# master.net
KiCad netlist of a schematic drawn in EAGLE
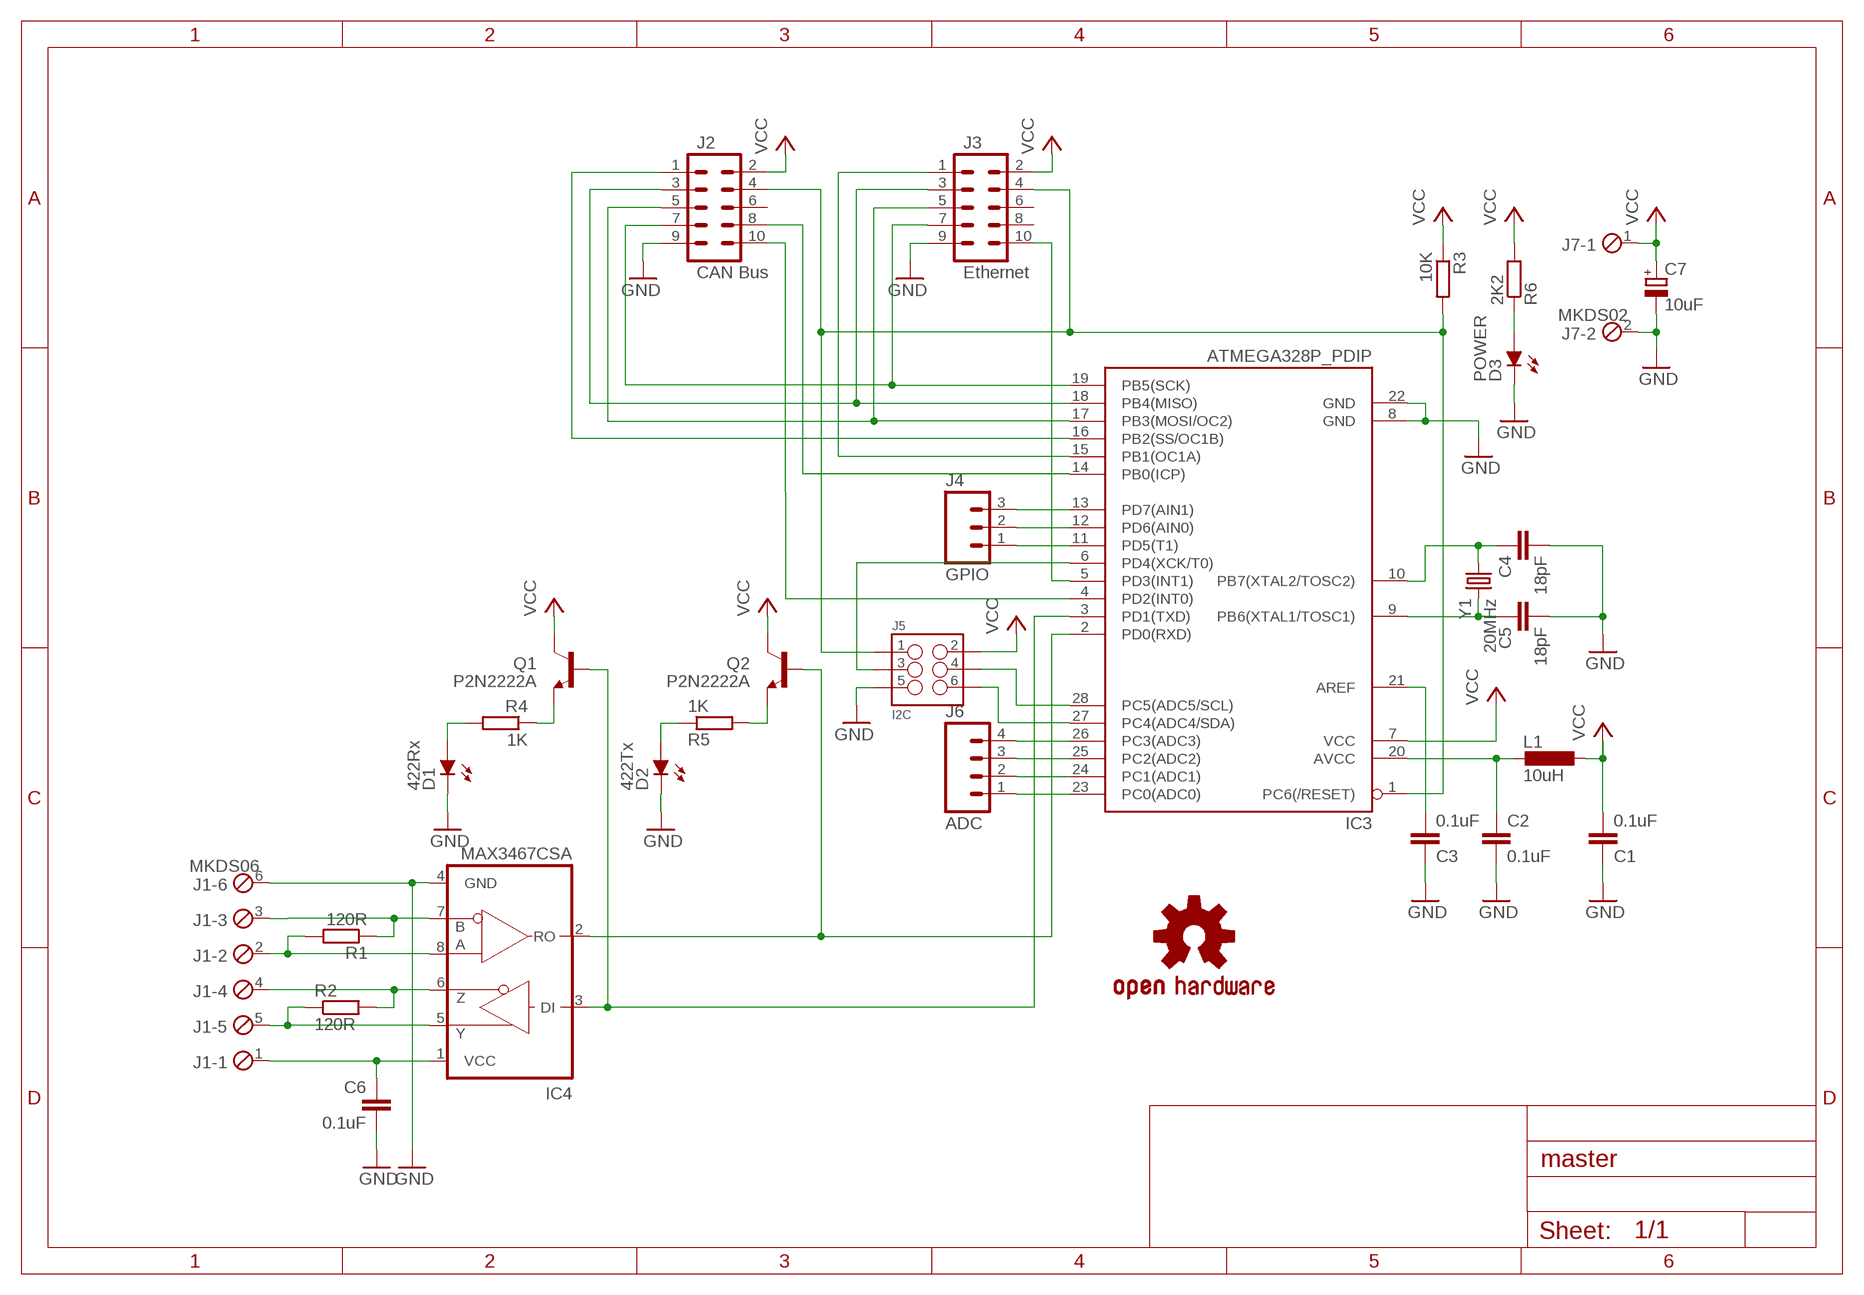
[diagram p0: schematic, sheet 1]

(export (version "E")
  (design (tool "Eeschema 10.0.6"))
  (components
    (comp (ref "C1")
      (value "0.1uF")
      (footprint "eagle-import:C050-025X075")
      (libsource (lib "eagle-import") (part "C-EU050-025X075"))
    )
    (comp (ref "C2")
      (value "0.1uF")
      (footprint "eagle-import:C050-025X075")
      (libsource (lib "eagle-import") (part "C-EU050-025X075"))
    )
    (comp (ref "C3")
      (value "0.1uF")
      (footprint "eagle-import:C050-025X075")
      (libsource (lib "eagle-import") (part "C-EU050-025X075"))
    )
    (comp (ref "C4")
      (value "18pF")
      (footprint "eagle-import:C050-024X044")
      (libsource (lib "eagle-import") (part "C-EU050-024X044"))
    )
    (comp (ref "C5")
      (value "18pF")
      (footprint "eagle-import:C050-024X044")
      (libsource (lib "eagle-import") (part "C-EU050-024X044"))
    )
    (comp (ref "C6")
      (value "0.1uF")
      (footprint "eagle-import:C050-025X075")
      (libsource (lib "eagle-import") (part "C-EU050-025X075"))
    )
    (comp (ref "C7")
      (value "10uF")
      (footprint "eagle-import:E2,5-6")
      (libsource (lib "eagle-import") (part "CPOL-EUE2.5-6"))
    )
    (comp (ref "D1")
      (value "422Rx")
      (footprint "eagle-import:LED3MM")
      (libsource (lib "eagle-import") (part "LED3MM"))
    )
    (comp (ref "D2")
      (value "422Tx")
      (footprint "eagle-import:LED3MM")
      (libsource (lib "eagle-import") (part "LED3MM"))
    )
    (comp (ref "D3")
      (value "POWER")
      (footprint "eagle-import:LED3MM")
      (libsource (lib "eagle-import") (part "LED3MM"))
    )
    (comp (ref "IC3")
      (value "ATMEGA328P_PDIP")
      (footprint "eagle-import:DIL28-3")
      (libsource (lib "eagle-import") (part "ATMEGA328P_PDIP"))
    )
    (comp (ref "IC4")
      (value "MAX3467CSA")
      (footprint "eagle-import:DIL08")
      (libsource (lib "eagle-import") (part "MAX3467SAC"))
    )
    (comp (ref "J1")
      (value "MKDS06")
      (footprint "eagle-import:MKDS06")
      (libsource (lib "eagle-import") (part "MKDS06"))
    )
    (comp (ref "J2")
      (value "CAN Bus")
      (footprint "eagle-import:2X5-SHROUDED")
      (libsource (lib "eagle-import") (part "M05X2SHD"))
    )
    (comp (ref "J3")
      (value "Ethernet")
      (footprint "eagle-import:2X5-SHROUDED")
      (libsource (lib "eagle-import") (part "M05X2SHD"))
    )
    (comp (ref "J4")
      (value "GPIO")
      (footprint "eagle-import:1X03")
      (libsource (lib "eagle-import") (part "M03PTH"))
    )
    (comp (ref "J5")
      (value "I2C")
      (footprint "eagle-import:2X3-SHROUDED")
      (libsource (lib "eagle-import") (part "M03X2SHROUD"))
    )
    (comp (ref "J6")
      (value "ADC")
      (footprint "eagle-import:1X04")
      (libsource (lib "eagle-import") (part "M04PTH"))
    )
    (comp (ref "J7")
      (value "MKDS02")
      (footprint "eagle-import:MKDS02")
      (libsource (lib "eagle-import") (part "MKDS02"))
    )
    (comp (ref "L1")
      (value "10uH")
      (footprint "eagle-import:0207_5V")
      (libsource (lib "eagle-import") (part "L-EU0207/5V"))
    )
    (comp (ref "LOGO1")
      (value "OSHW-LOGOM")
      (footprint "eagle-import:OSHW-LOGO-M")
      (libsource (lib "eagle-import") (part "OSHW-LOGOM"))
    )
    (comp (ref "Q1")
      (value "P2N2222A")
      (footprint "eagle-import:TO92")
      (libsource (lib "eagle-import") (part "P2N2222A"))
    )
    (comp (ref "Q2")
      (value "P2N2222A")
      (footprint "eagle-import:TO92")
      (libsource (lib "eagle-import") (part "P2N2222A"))
    )
    (comp (ref "R1")
      (value "120R")
      (footprint "eagle-import:0207_5V")
      (libsource (lib "eagle-import") (part "R-EU_0207/5V"))
    )
    (comp (ref "R2")
      (value "120R")
      (footprint "eagle-import:0207_5V")
      (libsource (lib "eagle-import") (part "R-EU_0207/5V"))
    )
    (comp (ref "R3")
      (value "10K")
      (footprint "eagle-import:0207_5V")
      (libsource (lib "eagle-import") (part "R-EU_0207/5V"))
    )
    (comp (ref "R4")
      (value "1K")
      (footprint "eagle-import:0207_5V")
      (libsource (lib "eagle-import") (part "R-EU_0207/5V"))
    )
    (comp (ref "R5")
      (value "1K")
      (footprint "eagle-import:0207_5V")
      (libsource (lib "eagle-import") (part "R-EU_0207/5V"))
    )
    (comp (ref "R6")
      (value "2K2")
      (footprint "eagle-import:0207_5V")
      (libsource (lib "eagle-import") (part "R-EU_0207/5V"))
    )
    (comp (ref "Y1")
      (value "20MHz")
      (footprint "eagle-import:HC49_S")
      (libsource (lib "eagle-import") (part "CRYSTALHC49S"))
    )
  )
  (nets
    (net (code "1") (name "GND") (class "Default")
      (node (ref "C1") (pin "1") (pinfunction "1_1") (pintype "passive"))
      (node (ref "C2") (pin "2") (pinfunction "2_2") (pintype "passive"))
      (node (ref "C3") (pin "1") (pinfunction "1_1") (pintype "passive"))
      (node (ref "C4") (pin "2") (pinfunction "2_2") (pintype "passive"))
      (node (ref "C5") (pin "2") (pinfunction "2_2") (pintype "passive"))
      (node (ref "C6") (pin "2") (pinfunction "2_2") (pintype "passive"))
      (node (ref "C7") (pin "-") (pinfunction "-_-") (pintype "passive"))
      (node (ref "D1") (pin "K") (pinfunction "C_K") (pintype "passive"))
      (node (ref "D2") (pin "K") (pinfunction "C_K") (pintype "passive"))
      (node (ref "D3") (pin "K") (pinfunction "C_K") (pintype "passive"))
      (node (ref "IC3") (pin "22") (pinfunction "GND_22") (pintype "bidirectional"))
      (node (ref "IC3") (pin "8") (pinfunction "GND_8") (pintype "bidirectional"))
      (node (ref "IC4") (pin "4") (pinfunction "GND_4") (pintype "power_in"))
      (node (ref "J1") (pin "6") (pinfunction "1_6") (pintype "passive"))
      (node (ref "J2") (pin "9") (pinfunction "9_9") (pintype "passive"))
      (node (ref "J3") (pin "9") (pinfunction "9_9") (pintype "passive"))
      (node (ref "J5") (pin "5") (pinfunction "5_5") (pintype "bidirectional"))
      (node (ref "J7") (pin "2") (pinfunction "1_2") (pintype "passive"))
    )
    (net (code "2") (name "Net-(D1-PadA)") (class "Default")
      (node (ref "D1") (pin "A") (pinfunction "A_A") (pintype "passive"))
      (node (ref "R4") (pin "2") (pinfunction "2_2") (pintype "passive"))
    )
    (net (code "3") (name "Net-(D2-PadA)") (class "Default")
      (node (ref "D2") (pin "A") (pinfunction "A_A") (pintype "passive"))
      (node (ref "R5") (pin "1") (pinfunction "1_1") (pintype "passive"))
    )
    (net (code "4") (name "Net-(D3-PadA)") (class "Default")
      (node (ref "D3") (pin "A") (pinfunction "A_A") (pintype "passive"))
      (node (ref "R6") (pin "1") (pinfunction "1_1") (pintype "passive"))
    )
    (net (code "5") (name "Net-(IC3-AREF)") (class "Default")
      (node (ref "C3") (pin "2") (pinfunction "2_2") (pintype "passive"))
      (node (ref "IC3") (pin "21") (pinfunction "AREF_21") (pintype "bidirectional"))
    )
    (net (code "6") (name "Net-(IC3-AVCC)") (class "Default")
      (node (ref "C2") (pin "1") (pinfunction "1_1") (pintype "passive"))
      (node (ref "IC3") (pin "20") (pinfunction "AVCC_20") (pintype "bidirectional"))
      (node (ref "L1") (pin "2") (pinfunction "2_2") (pintype "passive"))
    )
    (net (code "7") (name "Net-(IC3-PB0(ICP))") (class "Default")
      (node (ref "IC3") (pin "14") (pinfunction "PB0(ICP)_14") (pintype "bidirectional"))
      (node (ref "J2") (pin "8") (pinfunction "8_8") (pintype "passive"))
    )
    (net (code "8") (name "Net-(IC3-PB1(OC1A))") (class "Default")
      (node (ref "IC3") (pin "15") (pinfunction "PB1(OC1A)_15") (pintype "bidirectional"))
      (node (ref "J3") (pin "1") (pinfunction "1_1") (pintype "passive"))
    )
    (net (code "9") (name "Net-(IC3-PB2(SS{slash}OC1B))") (class "Default")
      (node (ref "IC3") (pin "16") (pinfunction "PB2(SS/OC1B)_16") (pintype "bidirectional"))
      (node (ref "J2") (pin "1") (pinfunction "1_1") (pintype "passive"))
    )
    (net (code "10") (name "Net-(IC3-PB3(MOSI{slash}OC2))") (class "Default")
      (node (ref "IC3") (pin "17") (pinfunction "PB3(MOSI/OC2)_17") (pintype "bidirectional"))
      (node (ref "J2") (pin "5") (pinfunction "5_5") (pintype "passive"))
      (node (ref "J3") (pin "5") (pinfunction "5_5") (pintype "passive"))
    )
    (net (code "11") (name "Net-(IC3-PB4(MISO))") (class "Default")
      (node (ref "IC3") (pin "18") (pinfunction "PB4(MISO)_18") (pintype "bidirectional"))
      (node (ref "J2") (pin "3") (pinfunction "3_3") (pintype "passive"))
      (node (ref "J3") (pin "3") (pinfunction "3_3") (pintype "passive"))
    )
    (net (code "12") (name "Net-(IC3-PB5(SCK))") (class "Default")
      (node (ref "IC3") (pin "19") (pinfunction "PB5(SCK)_19") (pintype "bidirectional"))
      (node (ref "J2") (pin "7") (pinfunction "7_7") (pintype "passive"))
      (node (ref "J3") (pin "7") (pinfunction "7_7") (pintype "passive"))
    )
    (net (code "13") (name "Net-(IC3-PB6(XTAL1{slash}TOSC1))") (class "Default")
      (node (ref "C5") (pin "1") (pinfunction "1_1") (pintype "passive"))
      (node (ref "IC3") (pin "9") (pinfunction "PB6(XTAL1/TOSC1)_9") (pintype "bidirectional"))
      (node (ref "Y1") (pin "2") (pinfunction "2_2") (pintype "passive"))
    )
    (net (code "14") (name "Net-(IC3-PB7(XTAL2{slash}TOSC2))") (class "Default")
      (node (ref "C4") (pin "1") (pinfunction "1_1") (pintype "passive"))
      (node (ref "IC3") (pin "10") (pinfunction "PB7(XTAL2/TOSC2)_10") (pintype "bidirectional"))
      (node (ref "Y1") (pin "1") (pinfunction "1_1") (pintype "passive"))
    )
    (net (code "15") (name "Net-(IC3-PC0(ADC0))") (class "Default")
      (node (ref "IC3") (pin "23") (pinfunction "PC0(ADC0)_23") (pintype "bidirectional"))
      (node (ref "J6") (pin "1") (pinfunction "1_1") (pintype "passive"))
    )
    (net (code "16") (name "Net-(IC3-PC1(ADC1))") (class "Default")
      (node (ref "IC3") (pin "24") (pinfunction "PC1(ADC1)_24") (pintype "bidirectional"))
      (node (ref "J6") (pin "2") (pinfunction "2_2") (pintype "passive"))
    )
    (net (code "17") (name "Net-(IC3-PC2(ADC2))") (class "Default")
      (node (ref "IC3") (pin "25") (pinfunction "PC2(ADC2)_25") (pintype "bidirectional"))
      (node (ref "J6") (pin "3") (pinfunction "3_3") (pintype "passive"))
    )
    (net (code "18") (name "Net-(IC3-PC3(ADC3))") (class "Default")
      (node (ref "IC3") (pin "26") (pinfunction "PC3(ADC3)_26") (pintype "bidirectional"))
      (node (ref "J6") (pin "4") (pinfunction "4_4") (pintype "passive"))
    )
    (net (code "19") (name "Net-(IC3-PC4(ADC4{slash}SDA))") (class "Default")
      (node (ref "IC3") (pin "27") (pinfunction "PC4(ADC4/SDA)_27") (pintype "bidirectional"))
      (node (ref "J5") (pin "6") (pinfunction "6_6") (pintype "bidirectional"))
    )
    (net (code "20") (name "Net-(IC3-PC5(ADC5{slash}SCL))") (class "Default")
      (node (ref "IC3") (pin "28") (pinfunction "PC5(ADC5/SCL)_28") (pintype "bidirectional"))
      (node (ref "J5") (pin "4") (pinfunction "4_4") (pintype "bidirectional"))
    )
    (net (code "21") (name "Net-(IC3-PC6({slash}RESET))") (class "Default")
      (node (ref "IC3") (pin "1") (pinfunction "PC6(/RESET)_1") (pintype "bidirectional"))
      (node (ref "J2") (pin "4") (pinfunction "4_4") (pintype "passive"))
      (node (ref "J3") (pin "4") (pinfunction "4_4") (pintype "passive"))
      (node (ref "J5") (pin "1") (pinfunction "1_1") (pintype "bidirectional"))
      (node (ref "R3") (pin "2") (pinfunction "2_2") (pintype "passive"))
    )
    (net (code "22") (name "Net-(IC3-PD0(RXD))") (class "Default")
      (node (ref "IC3") (pin "2") (pinfunction "PD0(RXD)_2") (pintype "bidirectional"))
      (node (ref "IC4") (pin "2") (pinfunction "RO_2") (pintype "output"))
      (node (ref "Q2") (pin "2") (pinfunction "B_2") (pintype "passive"))
    )
    (net (code "23") (name "Net-(IC3-PD1(TXD))") (class "Default")
      (node (ref "IC3") (pin "3") (pinfunction "PD1(TXD)_3") (pintype "bidirectional"))
      (node (ref "IC4") (pin "3") (pinfunction "DI_3") (pintype "input"))
      (node (ref "Q1") (pin "2") (pinfunction "B_2") (pintype "passive"))
    )
    (net (code "24") (name "Net-(IC3-PD2(INT0))") (class "Default")
      (node (ref "IC3") (pin "4") (pinfunction "PD2(INT0)_4") (pintype "bidirectional"))
      (node (ref "J2") (pin "10") (pinfunction "10_10") (pintype "passive"))
    )
    (net (code "25") (name "Net-(IC3-PD3(INT1))") (class "Default")
      (node (ref "IC3") (pin "5") (pinfunction "PD3(INT1)_5") (pintype "bidirectional"))
      (node (ref "J3") (pin "10") (pinfunction "10_10") (pintype "passive"))
    )
    (net (code "26") (name "Net-(IC3-PD4(XCK{slash}T0))") (class "Default")
      (node (ref "IC3") (pin "6") (pinfunction "PD4(XCK/T0)_6") (pintype "bidirectional"))
      (node (ref "J5") (pin "3") (pinfunction "3_3") (pintype "bidirectional"))
    )
    (net (code "27") (name "Net-(IC3-PD5(T1))") (class "Default")
      (node (ref "IC3") (pin "11") (pinfunction "PD5(T1)_11") (pintype "bidirectional"))
      (node (ref "J4") (pin "1") (pinfunction "1_1") (pintype "passive"))
    )
    (net (code "28") (name "Net-(IC3-PD6(AIN0))") (class "Default")
      (node (ref "IC3") (pin "12") (pinfunction "PD6(AIN0)_12") (pintype "bidirectional"))
      (node (ref "J4") (pin "2") (pinfunction "2_2") (pintype "passive"))
    )
    (net (code "29") (name "Net-(IC3-PD7(AIN1))") (class "Default")
      (node (ref "IC3") (pin "13") (pinfunction "PD7(AIN1)_13") (pintype "bidirectional"))
      (node (ref "J4") (pin "3") (pinfunction "3_3") (pintype "passive"))
    )
    (net (code "30") (name "Net-(IC4-A)") (class "Default")
      (node (ref "IC4") (pin "8") (pinfunction "A_8") (pintype "passive"))
      (node (ref "J1") (pin "2") (pinfunction "1_2") (pintype "passive"))
      (node (ref "R1") (pin "2") (pinfunction "2_2") (pintype "passive"))
    )
    (net (code "31") (name "Net-(IC4-B)") (class "Default")
      (node (ref "IC4") (pin "7") (pinfunction "B_7") (pintype "passive"))
      (node (ref "J1") (pin "3") (pinfunction "1_3") (pintype "passive"))
      (node (ref "R1") (pin "1") (pinfunction "1_1") (pintype "passive"))
    )
    (net (code "32") (name "Net-(IC4-VCC)") (class "Default")
      (node (ref "C6") (pin "1") (pinfunction "1_1") (pintype "passive"))
      (node (ref "IC4") (pin "1") (pinfunction "VCC_1") (pintype "power_in"))
      (node (ref "J1") (pin "1") (pinfunction "1_1") (pintype "passive"))
    )
    (net (code "33") (name "Net-(IC4-Y)") (class "Default")
      (node (ref "IC4") (pin "5") (pinfunction "Y_5") (pintype "passive"))
      (node (ref "J1") (pin "5") (pinfunction "1_5") (pintype "passive"))
      (node (ref "R2") (pin "1") (pinfunction "1_1") (pintype "passive"))
    )
    (net (code "34") (name "Net-(IC4-Z)") (class "Default")
      (node (ref "IC4") (pin "6") (pinfunction "Z_6") (pintype "passive"))
      (node (ref "J1") (pin "4") (pinfunction "1_4") (pintype "passive"))
      (node (ref "R2") (pin "2") (pinfunction "2_2") (pintype "passive"))
    )
    (net (code "35") (name "Net-(Q1-E)") (class "Default")
      (node (ref "Q1") (pin "1") (pinfunction "E_1") (pintype "passive"))
      (node (ref "R4") (pin "1") (pinfunction "1_1") (pintype "passive"))
    )
    (net (code "36") (name "Net-(Q2-E)") (class "Default")
      (node (ref "Q2") (pin "1") (pinfunction "E_1") (pintype "passive"))
      (node (ref "R5") (pin "2") (pinfunction "2_2") (pintype "passive"))
    )
    (net (code "37") (name "VCC") (class "Default")
      (node (ref "C1") (pin "2") (pinfunction "2_2") (pintype "passive"))
      (node (ref "C7") (pin "+") (pinfunction "+_+") (pintype "passive"))
      (node (ref "IC3") (pin "7") (pinfunction "VCC_7") (pintype "bidirectional"))
      (node (ref "J2") (pin "2") (pinfunction "2_2") (pintype "passive"))
      (node (ref "J3") (pin "2") (pinfunction "2_2") (pintype "passive"))
      (node (ref "J5") (pin "2") (pinfunction "2_2") (pintype "bidirectional"))
      (node (ref "J7") (pin "1") (pinfunction "1_1") (pintype "passive"))
      (node (ref "L1") (pin "1") (pinfunction "1_1") (pintype "passive"))
      (node (ref "Q1") (pin "3") (pinfunction "C_3") (pintype "passive"))
      (node (ref "Q2") (pin "3") (pinfunction "C_3") (pintype "passive"))
      (node (ref "R3") (pin "1") (pinfunction "1_1") (pintype "passive"))
      (node (ref "R6") (pin "2") (pinfunction "2_2") (pintype "passive"))
    )
    (net (code "38") (name "unconnected-(J2-Pad6)") (class "Default")
      (node (ref "J2") (pin "6") (pinfunction "6_6") (pintype "passive"))
    )
    (net (code "39") (name "unconnected-(J3-Pad6)") (class "Default")
      (node (ref "J3") (pin "6") (pinfunction "6_6") (pintype "passive"))
    )
    (net (code "40") (name "unconnected-(J3-Pad8)") (class "Default")
      (node (ref "J3") (pin "8") (pinfunction "8_8") (pintype "passive"))
    )
  )
)
